# 5Vdc.net
KiCad netlist of a schematic drawn in Altium Designer
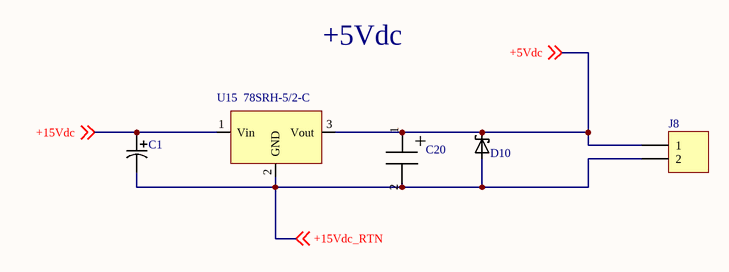
[diagram p0: +5Vdc.SchDoc]

(export (version "E")
  (design (tool "Eeschema 10.0.6"))
  (components
    (comp (ref "C1")
      (value "UBC1H470MNS1GS")
      (footprint "UBC1H470MNS1GS")
      (description "MD 50volts 47uF")
      (libsource (lib "Schlib1") (part "Nichicon electrolitic capacitor"))
    )
    (comp (ref "C20")
      (value "10SVPC120M")
      (footprint "PANASONIC SVPC SERIES")
      (description "10volts 120uF ESR 27mohm")
      (libsource (lib "Schlib1") (part "Panasonic electrolitic cap SVPC"))
    )
    (comp (ref "D10")
      (value "SMCJ5.0A")
      (footprint "TVS Diode DO-214AB-2 (SMC)")
      (description "SMC do-214AB-2")
      (libsource (lib "Schlib1") (part "TVS SMCJxxA"))
    )
    (comp (ref "J8")
      (value "Header 2")
      (footprint "HDR1X2")
      (description "Header, 2-Pin")
      (fields (field (name "PUBLISHER") "Altium Limited"))
      (libsource (lib "Miscellaneous Connectors") (part "Header 2"))
    )
    (comp (ref "U15")
      (value "78SRH-5/2-C")
      (footprint "78SR-5/2-C")
      (description "Convertidores CC/CC no aislados 8-32Vin 5Vout 2A SIP Switching Reg.")
      (libsource (lib "Schlib1") (part "78SR-5/2-C"))
    )
  )
  (nets
    (net (code "1") (name "+5Vdc") (class "Default")
      (node (ref "C20") (pin "1") (pintype "passive"))
      (node (ref "D10") (pin "C") (pinfunction "C_C") (pintype "passive"))
      (node (ref "J8") (pin "1") (pinfunction "1_1") (pintype "passive"))
      (node (ref "U15") (pin "3") (pinfunction "Vout_3") (pintype "passive"))
    )
    (net (code "2") (name "+15Vdc") (class "Default")
      (node (ref "C1") (pin "1") (pinfunction "1_1") (pintype "passive"))
      (node (ref "U15") (pin "1") (pinfunction "Vin_1") (pintype "passive"))
    )
    (net (code "3") (name "+15Vdc_RTN") (class "Default")
      (node (ref "C1") (pin "2") (pinfunction "2_2") (pintype "passive"))
      (node (ref "C20") (pin "2") (pintype "passive"))
      (node (ref "D10") (pin "A") (pinfunction "1_A") (pintype "passive"))
      (node (ref "J8") (pin "2") (pinfunction "2_2") (pintype "passive"))
      (node (ref "U15") (pin "2") (pinfunction "GND_2") (pintype "passive"))
    )
  )
)
